# ESP32.net
KiCad netlist of a schematic drawn in Altium Designer
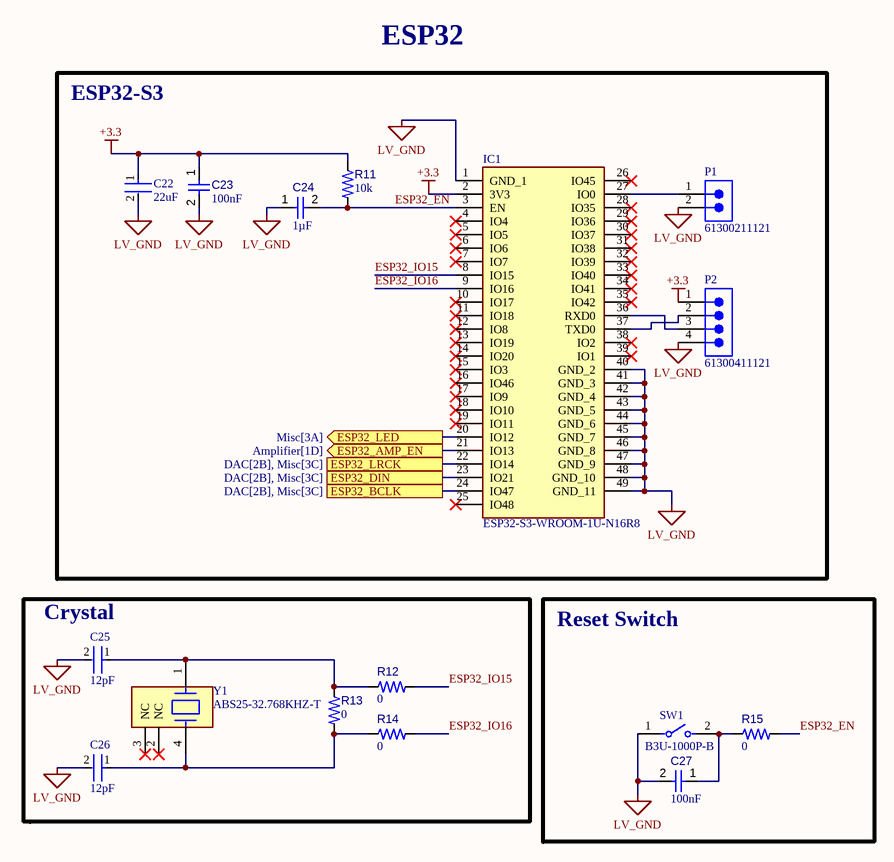
[diagram p0: ESP32.SchDoc]

(export (version "E")
  (design (tool "Eeschema 10.0.6"))
  (components
    (comp (ref "C22")
      (value "22uF")
      (footprint "FP-GRM188-0_2-IPC_C")
      (description "Chip Multilayer Ceramic Capacitors for General Purpose, 0603, 22uF, X5R, 15%, 20%, 10V")
      (fields (field (name "TOLERANCE") "20%"))
      (libsource (lib "Altium Content Vault") (part "11868f565c42a9108669ba33697ecf6"))
    )
    (comp (ref "C23")
      (value "100nF")
      (footprint "FP-0603-L_1_6_0_15-W_0_81-IPC_C")
      (fields (field (name "Comment") "06035C104K4T2A"))
      (libsource (lib "Spartan Racing Altium Workspace") (part "CAP-NP-2"))
    )
    (comp (ref "C24")
      (value "1µF")
      (footprint "CAPC0603(1608)100_L")
      (description "Chip Capacitor, 1µF +/-0.1%, 25V, 0603, Thickness 1 mm")
      (fields (field (name "TOLERANCE") "20%") (field (name "Comment") "Capacitor 1µF +/-0.1% 25V 0603"))
      (libsource (lib "Spartan Racing Altium Workspace") (part "CAP-NP-2"))
    )
    (comp (ref "C25")
      (value "12pF")
      (footprint "FP-C0603C-CF-MFG")
      (description "Ceramic Capacitor 12Pf 50V, C0G, 5%, 0603, Full Reel")
      (fields (field (name "MANUFACTURER") "KEMET") (field (name "TOLERANCE") "0.05"))
      (libsource (lib "Altium Content Vault") (part "b4654b650e69147ec39a6b967a45e02"))
    )
    (comp (ref "C26")
      (value "12pF")
      (footprint "FP-C0603C-CF-MFG")
      (description "Ceramic Capacitor 12Pf 50V, C0G, 5%, 0603, Full Reel")
      (fields (field (name "MANUFACTURER") "KEMET") (field (name "TOLERANCE") "0.05"))
      (libsource (lib "Altium Content Vault") (part "b4654b650e69147ec39a6b967a45e02"))
    )
    (comp (ref "C27")
      (value "100nF")
      (footprint "FP-0603-L_1_6_0_15-W_0_81-IPC_C")
      (fields (field (name "Comment") "06035C104K4T2A"))
      (libsource (lib "Spartan Racing Altium Workspace") (part "CAP-NP-2"))
    )
    (comp (ref "IC1")
      (value "ESP32-S3-WROOM-1U-N16R8")
      (footprint "SamacSys:ESP32S3WROOM1UN16R8")
      (description "Integrated Circuit")
      (fields (field (name "MOUSER PART NUMBER") "356-ESP32S3WM1UN16R8"))
      (libsource (lib "*") (part "ESP32-S3-WROOM-1U-N16R8"))
    )
    (comp (ref "P1")
      (value "61300211121")
      (footprint "61300211121")
      (libsource (lib "Altium Content Vault") (part "Header_Male_1R_02P"))
    )
    (comp (ref "P2")
      (value "61300411121")
      (footprint "61300411121")
      (libsource (lib "Altium Content Vault") (part "Header_Male_1R_04P"))
    )
    (comp (ref "R11")
      (value "10k")
      (footprint "FP-CRCW0603-e3-IPC_C")
      (fields
        (field (name "TOLERANCE") "5%")
        (field (name "POWER") "100mW")
        (field (name "Comment") "CRCW060310K0JNEA")
      )
      (libsource (lib "Spartan Racing Altium Workspace") (part "1614881-3"))
    )
    (comp (ref "R12")
      (value "0")
      (footprint "RESC0603(1608)_L")
      (description "Jumper 0603")
      (libsource (lib "Spartan Racing Altium Workspace") (part "1614881-3"))
    )
    (comp (ref "R13")
      (value "0")
      (footprint "RESC0603(1608)_L")
      (description "Jumper 0603")
      (libsource (lib "Spartan Racing Altium Workspace") (part "1614881-3"))
    )
    (comp (ref "R14")
      (value "0")
      (footprint "RESC0603(1608)_L")
      (description "Jumper 0603")
      (libsource (lib "Spartan Racing Altium Workspace") (part "1614881-3"))
    )
    (comp (ref "R15")
      (value "0")
      (footprint "RESC0603(1608)_L")
      (description "Jumper 0603")
      (libsource (lib "Spartan Racing Altium Workspace") (part "1614881-3"))
    )
    (comp (ref "SW1")
      (value "B3U-1000P-B")
      (footprint "FP-B3U-1000P-B-MFG")
      (description "SWITCH TACTILE SPST-NO 0.05A 12V")
      (fields
        (field (name "OCTOPART") "https://octopart.com/b3u-1000p-b-omron-1057356")
        (field (name "MANUFACTURER") "Omron")
      )
      (libsource (lib "Altium Content Vault") (part "bb27bde45df87f1f469753f287ef5ae"))
    )
    (comp (ref "Y1")
      (value "ABS25-32.768KHZ-T")
      (footprint "FP-ABS25-MFG")
      (description "CRYSTAL 32.7680KHZ 12.5PF SMD")
      (fields (field (name "TOLERANCE") "20ppm"))
      (libsource (lib "Altium Content Vault") (part "d2378e42ab3755ffcd472789242ec61"))
    )
  )
  (nets
    (net (code "1") (name "+3.3") (class "Default")
      (node (ref "C22") (pin "1") (pinfunction "1_1") (pintype "passive"))
      (node (ref "C23") (pin "1") (pinfunction "1_1") (pintype "passive"))
      (node (ref "IC1") (pin "2") (pinfunction "3V3_2") (pintype "passive"))
      (node (ref "P2") (pin "1") (pinfunction "1_1") (pintype "passive"))
      (node (ref "R11") (pin "1") (pinfunction "1_1") (pintype "passive"))
    )
    (net (code "2") (name "/ESP32_AMP_EN") (class "Default")
      (node (ref "IC1") (pin "21") (pinfunction "IO13_21") (pintype "passive"))
    )
    (net (code "3") (name "/ESP32_BCLK") (class "Default")
      (node (ref "IC1") (pin "24") (pinfunction "IO47_24") (pintype "passive"))
    )
    (net (code "4") (name "/ESP32_DIN") (class "Default")
      (node (ref "IC1") (pin "23") (pinfunction "IO21_23") (pintype "passive"))
    )
    (net (code "5") (name "/ESP32_EN") (class "Default")
      (node (ref "C24") (pin "2") (pinfunction "2_2") (pintype "passive"))
      (node (ref "IC1") (pin "3") (pinfunction "EN_3") (pintype "passive"))
      (node (ref "R11") (pin "2") (pinfunction "2_2") (pintype "passive"))
      (node (ref "R15") (pin "2") (pinfunction "2_2") (pintype "passive"))
    )
    (net (code "6") (name "/ESP32_IO15") (class "Default")
      (node (ref "IC1") (pin "8") (pinfunction "IO15_8") (pintype "passive"))
      (node (ref "R12") (pin "2") (pinfunction "2_2") (pintype "passive"))
    )
    (net (code "7") (name "/ESP32_IO16") (class "Default")
      (node (ref "IC1") (pin "9") (pinfunction "IO16_9") (pintype "passive"))
      (node (ref "R14") (pin "2") (pinfunction "2_2") (pintype "passive"))
    )
    (net (code "8") (name "/ESP32_LED") (class "Default")
      (node (ref "IC1") (pin "20") (pinfunction "IO12_20") (pintype "passive"))
    )
    (net (code "9") (name "/ESP32_LRCK") (class "Default")
      (node (ref "IC1") (pin "22") (pinfunction "IO14_22") (pintype "passive"))
    )
    (net (code "10") (name "LV_GND") (class "Default")
      (node (ref "C22") (pin "2") (pinfunction "2_2") (pintype "passive"))
      (node (ref "C23") (pin "2") (pinfunction "2_2") (pintype "passive"))
      (node (ref "C24") (pin "1") (pinfunction "1_1") (pintype "passive"))
      (node (ref "C25") (pin "2") (pinfunction "2_2") (pintype "passive"))
      (node (ref "C26") (pin "2") (pinfunction "2_2") (pintype "passive"))
      (node (ref "C27") (pin "2") (pinfunction "2_2") (pintype "passive"))
      (node (ref "IC1") (pin "1") (pinfunction "GND_1_1") (pintype "passive"))
      (node (ref "IC1") (pin "40") (pinfunction "GND_2_40") (pintype "passive"))
      (node (ref "IC1") (pin "41") (pinfunction "GND_3_41") (pintype "passive"))
      (node (ref "IC1") (pin "42") (pinfunction "GND_4_42") (pintype "passive"))
      (node (ref "IC1") (pin "43") (pinfunction "GND_5_43") (pintype "passive"))
      (node (ref "IC1") (pin "44") (pinfunction "GND_6_44") (pintype "passive"))
      (node (ref "IC1") (pin "45") (pinfunction "GND_7_45") (pintype "passive"))
      (node (ref "IC1") (pin "46") (pinfunction "GND_8_46") (pintype "passive"))
      (node (ref "IC1") (pin "47") (pinfunction "GND_9_47") (pintype "passive"))
      (node (ref "IC1") (pin "48") (pinfunction "GND_10_48") (pintype "passive"))
      (node (ref "IC1") (pin "49") (pinfunction "GND_11_49") (pintype "passive"))
      (node (ref "P1") (pin "2") (pinfunction "2_2") (pintype "passive"))
      (node (ref "P2") (pin "4") (pinfunction "4_4") (pintype "passive"))
      (node (ref "SW1") (pin "1") (pinfunction "1_1") (pintype "passive"))
    )
    (net (code "11") (name "Net-(C25-Pad1)") (class "Default")
      (node (ref "C25") (pin "1") (pinfunction "1_1") (pintype "passive"))
      (node (ref "R12") (pin "1") (pinfunction "1_1") (pintype "passive"))
      (node (ref "R13") (pin "1") (pinfunction "1_1") (pintype "passive"))
      (node (ref "Y1") (pin "1") (pinfunction "1_1") (pintype "passive"))
    )
    (net (code "12") (name "Net-(C26-Pad1)") (class "Default")
      (node (ref "C26") (pin "1") (pinfunction "1_1") (pintype "passive"))
      (node (ref "R13") (pin "2") (pinfunction "2_2") (pintype "passive"))
      (node (ref "R14") (pin "1") (pinfunction "1_1") (pintype "passive"))
      (node (ref "Y1") (pin "4") (pinfunction "4_4") (pintype "passive"))
    )
    (net (code "13") (name "Net-(C27-Pad1)") (class "Default")
      (node (ref "C27") (pin "1") (pinfunction "1_1") (pintype "passive"))
      (node (ref "R15") (pin "1") (pinfunction "1_1") (pintype "passive"))
      (node (ref "SW1") (pin "2") (pinfunction "2_2") (pintype "passive"))
    )
    (net (code "14") (name "Net-(IC1-IO0)") (class "Default")
      (node (ref "IC1") (pin "27") (pinfunction "IO0_27") (pintype "passive"))
      (node (ref "P1") (pin "1") (pinfunction "1_1") (pintype "passive"))
    )
    (net (code "15") (name "Net-(IC1-RXD0)") (class "Default")
      (node (ref "IC1") (pin "36") (pinfunction "RXD0_36") (pintype "passive"))
      (node (ref "P2") (pin "3") (pinfunction "3_3") (pintype "passive"))
    )
    (net (code "16") (name "Net-(IC1-TXD0)") (class "Default")
      (node (ref "IC1") (pin "37") (pinfunction "TXD0_37") (pintype "passive"))
      (node (ref "P2") (pin "2") (pinfunction "2_2") (pintype "passive"))
    )
    (net (code "17") (name "unconnected-(IC1-IO1-Pad39)") (class "Default")
      (node (ref "IC1") (pin "39") (pinfunction "IO1_39") (pintype "passive+no_connect"))
    )
    (net (code "18") (name "unconnected-(IC1-IO2-Pad38)") (class "Default")
      (node (ref "IC1") (pin "38") (pinfunction "IO2_38") (pintype "passive+no_connect"))
    )
    (net (code "19") (name "unconnected-(IC1-IO3-Pad15)") (class "Default")
      (node (ref "IC1") (pin "15") (pinfunction "IO3_15") (pintype "passive+no_connect"))
    )
    (net (code "20") (name "unconnected-(IC1-IO4-Pad4)") (class "Default")
      (node (ref "IC1") (pin "4") (pinfunction "IO4_4") (pintype "passive+no_connect"))
    )
    (net (code "21") (name "unconnected-(IC1-IO5-Pad5)") (class "Default")
      (node (ref "IC1") (pin "5") (pinfunction "IO5_5") (pintype "passive+no_connect"))
    )
    (net (code "22") (name "unconnected-(IC1-IO6-Pad6)") (class "Default")
      (node (ref "IC1") (pin "6") (pinfunction "IO6_6") (pintype "passive+no_connect"))
    )
    (net (code "23") (name "unconnected-(IC1-IO7-Pad7)") (class "Default")
      (node (ref "IC1") (pin "7") (pinfunction "IO7_7") (pintype "passive+no_connect"))
    )
    (net (code "24") (name "unconnected-(IC1-IO8-Pad12)") (class "Default")
      (node (ref "IC1") (pin "12") (pinfunction "IO8_12") (pintype "passive+no_connect"))
    )
    (net (code "25") (name "unconnected-(IC1-IO9-Pad17)") (class "Default")
      (node (ref "IC1") (pin "17") (pinfunction "IO9_17") (pintype "passive+no_connect"))
    )
    (net (code "26") (name "unconnected-(IC1-IO10-Pad18)") (class "Default")
      (node (ref "IC1") (pin "18") (pinfunction "IO10_18") (pintype "passive+no_connect"))
    )
    (net (code "27") (name "unconnected-(IC1-IO11-Pad19)") (class "Default")
      (node (ref "IC1") (pin "19") (pinfunction "IO11_19") (pintype "passive+no_connect"))
    )
    (net (code "28") (name "unconnected-(IC1-IO17-Pad10)") (class "Default")
      (node (ref "IC1") (pin "10") (pinfunction "IO17_10") (pintype "passive+no_connect"))
    )
    (net (code "29") (name "unconnected-(IC1-IO18-Pad11)") (class "Default")
      (node (ref "IC1") (pin "11") (pinfunction "IO18_11") (pintype "passive+no_connect"))
    )
    (net (code "30") (name "unconnected-(IC1-IO19-Pad13)") (class "Default")
      (node (ref "IC1") (pin "13") (pinfunction "IO19_13") (pintype "passive+no_connect"))
    )
    (net (code "31") (name "unconnected-(IC1-IO20-Pad14)") (class "Default")
      (node (ref "IC1") (pin "14") (pinfunction "IO20_14") (pintype "passive+no_connect"))
    )
    (net (code "32") (name "unconnected-(IC1-IO35-Pad28)") (class "Default")
      (node (ref "IC1") (pin "28") (pinfunction "IO35_28") (pintype "passive+no_connect"))
    )
    (net (code "33") (name "unconnected-(IC1-IO36-Pad29)") (class "Default")
      (node (ref "IC1") (pin "29") (pinfunction "IO36_29") (pintype "passive+no_connect"))
    )
    (net (code "34") (name "unconnected-(IC1-IO37-Pad30)") (class "Default")
      (node (ref "IC1") (pin "30") (pinfunction "IO37_30") (pintype "passive+no_connect"))
    )
    (net (code "35") (name "unconnected-(IC1-IO38-Pad31)") (class "Default")
      (node (ref "IC1") (pin "31") (pinfunction "IO38_31") (pintype "passive+no_connect"))
    )
    (net (code "36") (name "unconnected-(IC1-IO39-Pad32)") (class "Default")
      (node (ref "IC1") (pin "32") (pinfunction "IO39_32") (pintype "passive+no_connect"))
    )
    (net (code "37") (name "unconnected-(IC1-IO40-Pad33)") (class "Default")
      (node (ref "IC1") (pin "33") (pinfunction "IO40_33") (pintype "passive+no_connect"))
    )
    (net (code "38") (name "unconnected-(IC1-IO41-Pad34)") (class "Default")
      (node (ref "IC1") (pin "34") (pinfunction "IO41_34") (pintype "passive+no_connect"))
    )
    (net (code "39") (name "unconnected-(IC1-IO42-Pad35)") (class "Default")
      (node (ref "IC1") (pin "35") (pinfunction "IO42_35") (pintype "passive+no_connect"))
    )
    (net (code "40") (name "unconnected-(IC1-IO45-Pad26)") (class "Default")
      (node (ref "IC1") (pin "26") (pinfunction "IO45_26") (pintype "passive+no_connect"))
    )
    (net (code "41") (name "unconnected-(IC1-IO46-Pad16)") (class "Default")
      (node (ref "IC1") (pin "16") (pinfunction "IO46_16") (pintype "passive+no_connect"))
    )
    (net (code "42") (name "unconnected-(IC1-IO48-Pad25)") (class "Default")
      (node (ref "IC1") (pin "25") (pinfunction "IO48_25") (pintype "passive+no_connect"))
    )
    (net (code "43") (name "unconnected-(Y1-NC-Pad2)") (class "Default")
      (node (ref "Y1") (pin "2") (pinfunction "NC_2") (pintype "passive+no_connect"))
    )
    (net (code "44") (name "unconnected-(Y1-NC-Pad3)") (class "Default")
      (node (ref "Y1") (pin "3") (pinfunction "NC_3") (pintype "passive+no_connect"))
    )
  )
)
